# Power_Supply.net
KiCad netlist of a schematic drawn in EAGLE
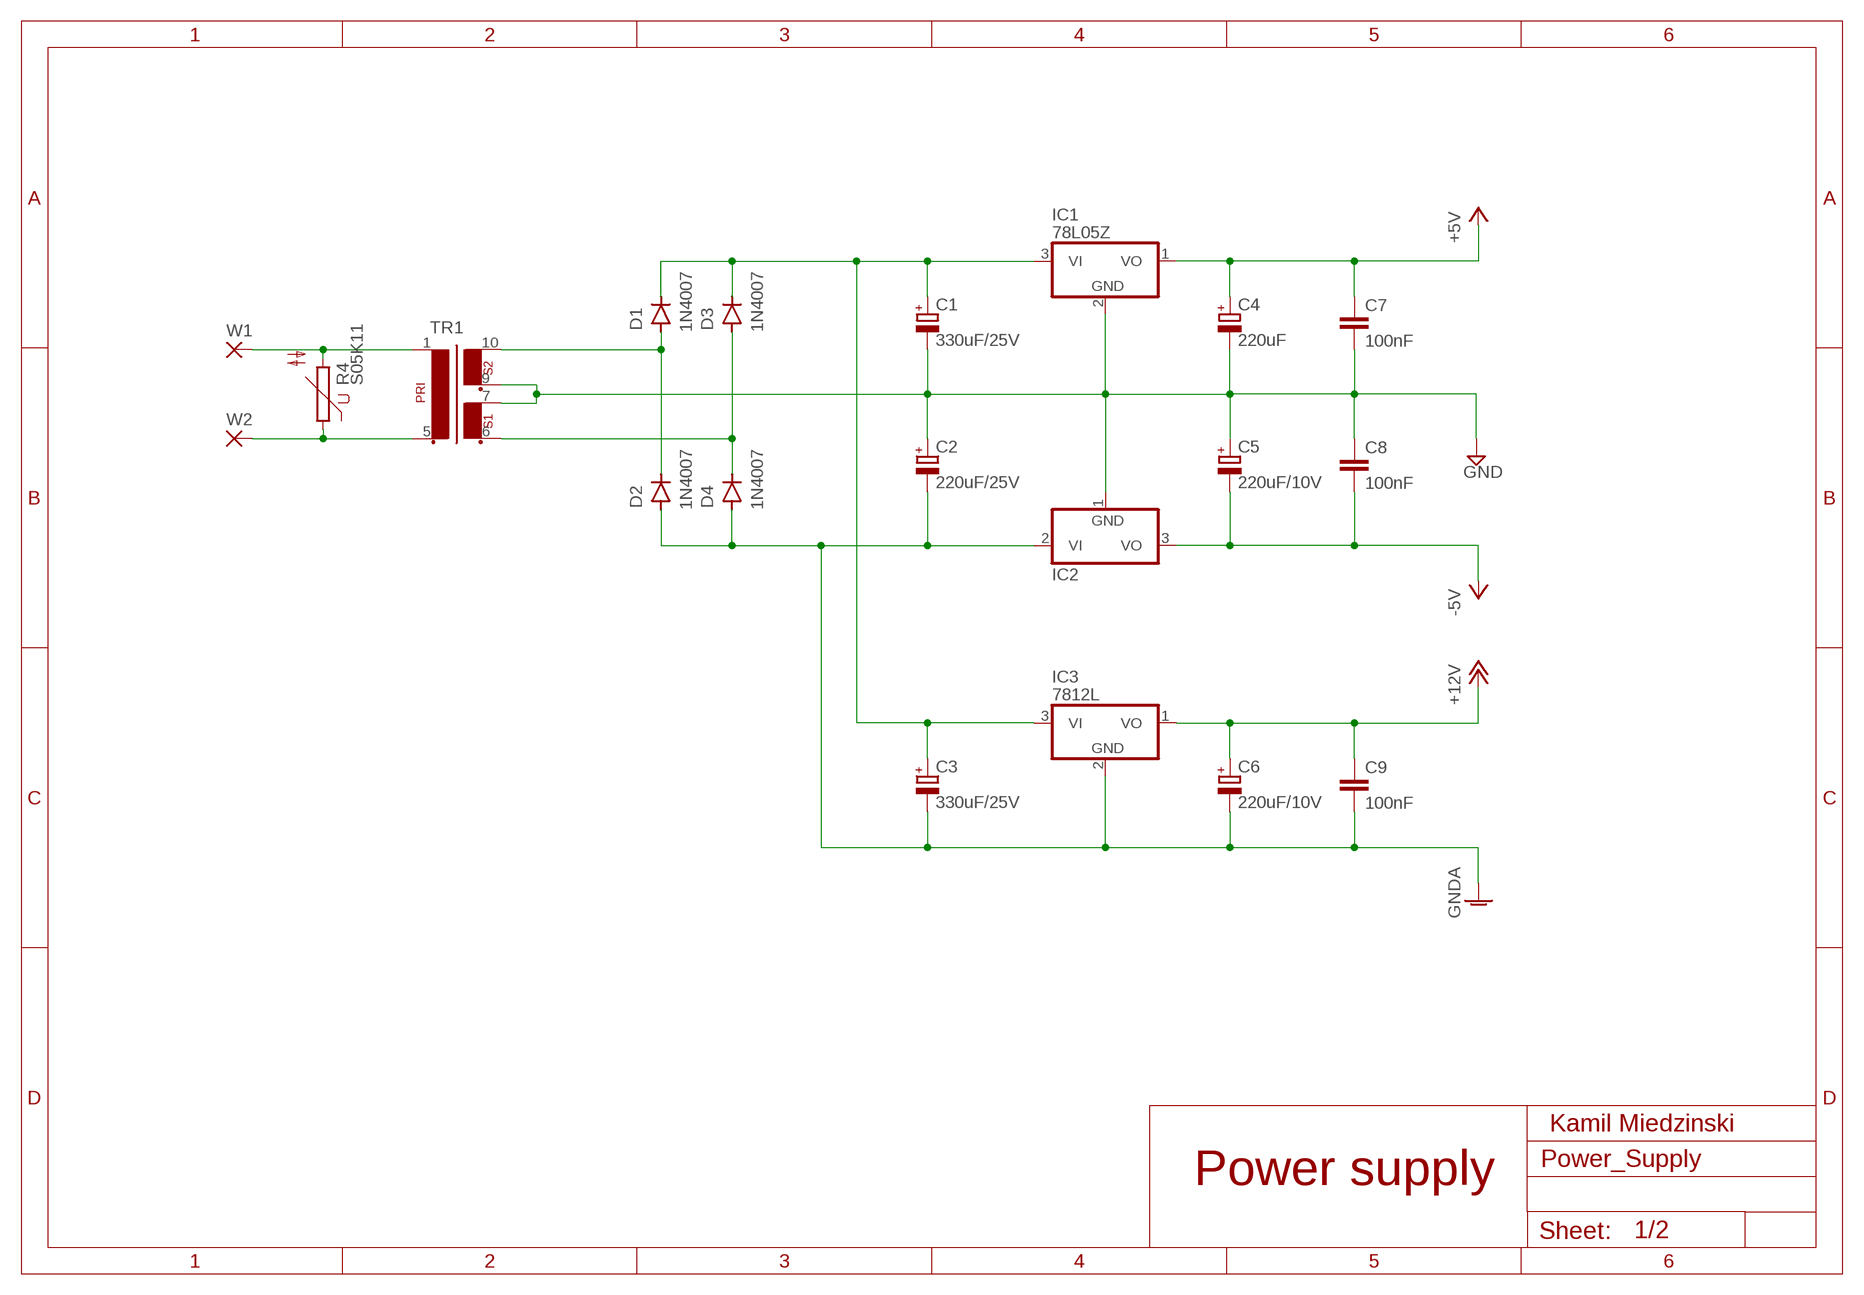
[diagram p0: schematic, sheet 1]
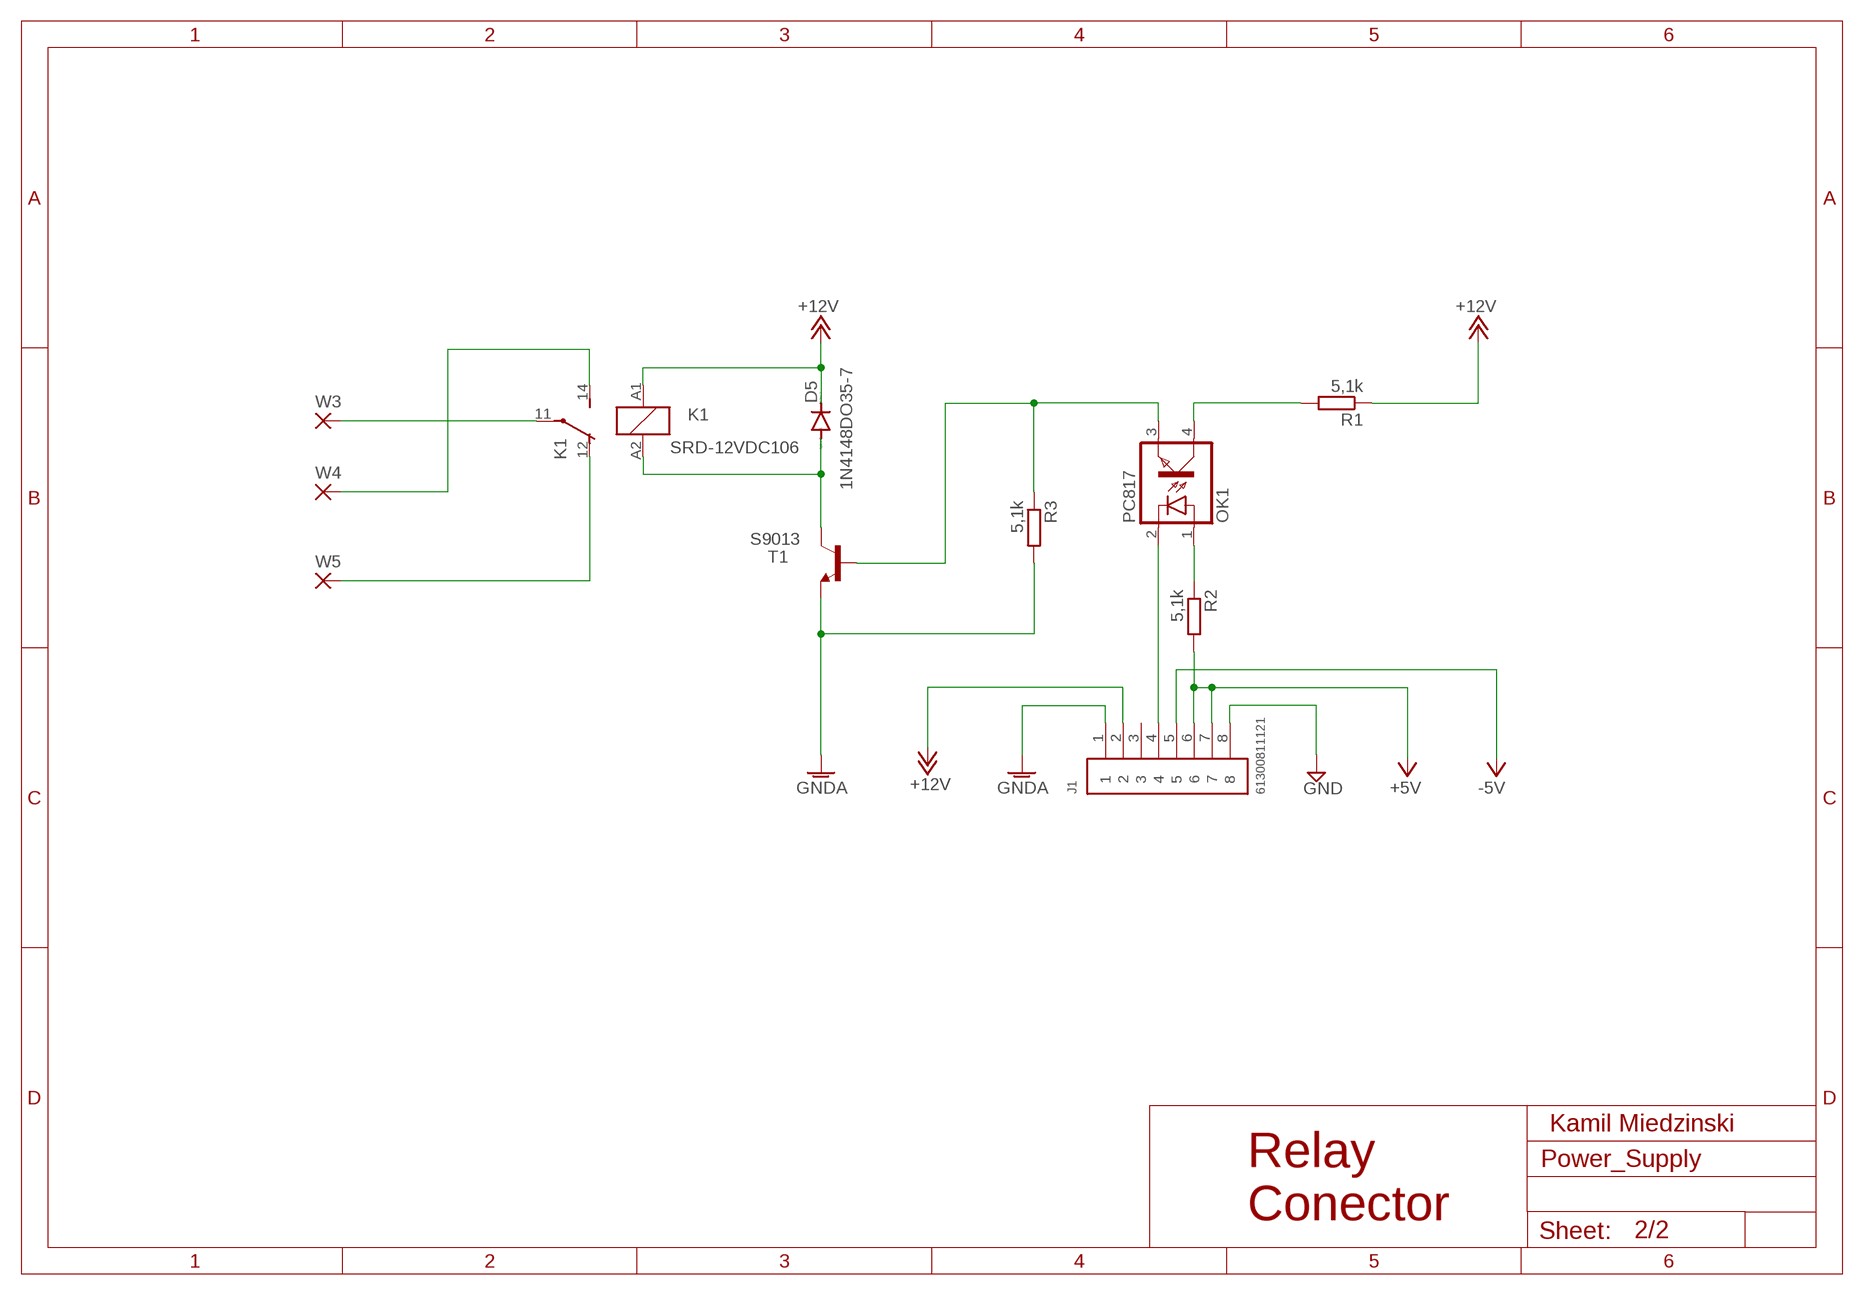
[diagram p1: schematic, sheet 2]

(export (version "E")
  (design (tool "Eeschema 10.0.6"))
  (components
    (comp (ref "D5")
      (value "1N4148DO35-7")
      (footprint "eagle-import:DO35-7")
      (libsource (lib "eagle-import") (part "1N4148DO35-7"))
    )
    (comp (ref "J1")
      (value "61300811121")
      (footprint "eagle-import:61300811121")
      (fields
        (field (name "DIGI_KEY_PART_NUMBER") "732-5321-ND")
        (field (name "MANUFACTURER") "Wurth Electronics Inc.")
        (field (name "CREATED_BY") "PCBLayout.com")
      )
      (libsource (lib "eagle-import") (part "61300811121"))
    )
    (comp (ref "K1")
      (value "SRD-12VDC106")
      (footprint "eagle-import:ZN5")
      (libsource (lib "eagle-import") (part "SRD-12VDC106"))
    )
    (comp (ref "OK1")
      (value "PC817")
      (footprint "eagle-import:DIL04")
      (fields (field (name "MPN") "PC817X4J000F"))
      (libsource (lib "eagle-import") (part "PC817"))
    )
    (comp (ref "R1")
      (value "5,1k")
      (footprint "eagle-import:0204_7")
      (libsource (lib "eagle-import") (part "R-EU_0204/7"))
    )
    (comp (ref "R2")
      (value "5,1k")
      (footprint "eagle-import:0204_7")
      (libsource (lib "eagle-import") (part "R-EU_0204/7"))
    )
    (comp (ref "R3")
      (value "5,1k")
      (footprint "eagle-import:0204_7")
      (libsource (lib "eagle-import") (part "R-EU_0204/7"))
    )
    (comp (ref "T1")
      (value "S9013")
      (footprint "eagle-import:TO92")
      (libsource (lib "eagle-import") (part "BC547"))
    )
    (comp (ref "W3")
      (value "PAD_4/7")
      (footprint "eagle-import:4_7")
      (libsource (lib "eagle-import") (part "PAD_4/7"))
    )
    (comp (ref "W4")
      (value "PAD_4/7")
      (footprint "eagle-import:4_7")
      (libsource (lib "eagle-import") (part "PAD_4/7"))
    )
    (comp (ref "W5")
      (value "PAD_4/7")
      (footprint "eagle-import:4_7")
      (libsource (lib "eagle-import") (part "PAD_4/7"))
    )
    (comp (ref "C1")
      (value "330uF/25V")
      (footprint "eagle-import:E3,5-8")
      (libsource (lib "eagle-import") (part "CPOL-EUE3.5-8"))
    )
    (comp (ref "C2")
      (value "220uF/25V")
      (footprint "eagle-import:E2,5-5")
      (libsource (lib "eagle-import") (part "CPOL-EUE2.5-5"))
    )
    (comp (ref "C3")
      (value "330uF/25V")
      (footprint "eagle-import:E3,5-8")
      (libsource (lib "eagle-import") (part "CPOL-EUE3.5-8"))
    )
    (comp (ref "C4")
      (value "220uF")
      (footprint "eagle-import:E2-4")
      (libsource (lib "eagle-import") (part "CPOL-EUE2-4"))
    )
    (comp (ref "C5")
      (value "220uF/10V")
      (footprint "eagle-import:E2-4")
      (libsource (lib "eagle-import") (part "CPOL-EUE2-4"))
    )
    (comp (ref "C6")
      (value "220uF/10V")
      (footprint "eagle-import:E2-4")
      (libsource (lib "eagle-import") (part "CPOL-EUE2-4"))
    )
    (comp (ref "C7")
      (value "100nF")
      (footprint "eagle-import:C025-024X044")
      (libsource (lib "eagle-import") (part "C-EU025-024X044"))
    )
    (comp (ref "C8")
      (value "100nF")
      (footprint "eagle-import:C025-024X044")
      (libsource (lib "eagle-import") (part "C-EU025-024X044"))
    )
    (comp (ref "C9")
      (value "100nF")
      (footprint "eagle-import:C025-024X044")
      (libsource (lib "eagle-import") (part "C-EU025-024X044"))
    )
    (comp (ref "D1")
      (value "1N4007")
      (footprint "eagle-import:DO-41")
      (fields
        (field (name "DIGIKEY_PART_NUMBER") "1N4007MSCT-ND")
        (field (name "MANUFACTURER") "Micro Commercial Co")
        (field (name "CREATED_BY") "PCBLayout.com")
      )
      (libsource (lib "eagle-import") (part "1N4007"))
    )
    (comp (ref "D2")
      (value "1N4007")
      (footprint "eagle-import:DO-41")
      (fields
        (field (name "DIGIKEY_PART_NUMBER") "1N4007MSCT-ND")
        (field (name "MANUFACTURER") "Micro Commercial Co")
        (field (name "CREATED_BY") "PCBLayout.com")
      )
      (libsource (lib "eagle-import") (part "1N4007"))
    )
    (comp (ref "D3")
      (value "1N4007")
      (footprint "eagle-import:DO-41")
      (fields
        (field (name "DIGIKEY_PART_NUMBER") "1N4007MSCT-ND")
        (field (name "MANUFACTURER") "Micro Commercial Co")
        (field (name "CREATED_BY") "PCBLayout.com")
      )
      (libsource (lib "eagle-import") (part "1N4007"))
    )
    (comp (ref "D4")
      (value "1N4007")
      (footprint "eagle-import:DO-41")
      (fields
        (field (name "DIGIKEY_PART_NUMBER") "1N4007MSCT-ND")
        (field (name "MANUFACTURER") "Micro Commercial Co")
        (field (name "CREATED_BY") "PCBLayout.com")
      )
      (libsource (lib "eagle-import") (part "1N4007"))
    )
    (comp (ref "IC1")
      (value "78L05Z")
      (footprint "eagle-import:TO92")
      (libsource (lib "eagle-import") (part "78ZL05"))
    )
    (comp (ref "IC2")
      (value "79L05Z")
      (footprint "eagle-import:TO92")
      (libsource (lib "eagle-import") (part "79ZL05"))
    )
    (comp (ref "IC3")
      (value "7812L")
      (footprint "eagle-import:TO92")
      (libsource (lib "eagle-import") (part "78L12"))
    )
    (comp (ref "R4")
      (value "S05K11")
      (footprint "eagle-import:S05K11")
      (libsource (lib "eagle-import") (part "S05K11"))
    )
    (comp (ref "TR1")
      (value "TEZ_2.0VA/230V/2X9V")
      (footprint "eagle-import:TEZ_2.0VA_230V_2X9V")
      (libsource (lib "eagle-import") (part "TEZ_2.0VA/230V/2X9V"))
    )
    (comp (ref "W1")
      (value "PAD_4/7")
      (footprint "eagle-import:4_7")
      (libsource (lib "eagle-import") (part "PAD_4/7"))
    )
    (comp (ref "W2")
      (value "PAD_4/7")
      (footprint "eagle-import:4_7")
      (libsource (lib "eagle-import") (part "PAD_4/7"))
    )
  )
  (nets
    (net (code "1") (name "+5V") (class "Default")
      (node (ref "C4") (pin "+") (pinfunction "+_+") (pintype "passive"))
      (node (ref "C7") (pin "1") (pinfunction "1_1") (pintype "passive"))
      (node (ref "IC1") (pin "1") (pinfunction "VO_1") (pintype "passive"))
      (node (ref "J1") (pin "6") (pinfunction "6_6") (pintype "passive"))
      (node (ref "J1") (pin "7") (pinfunction "7_7") (pintype "passive"))
      (node (ref "R2") (pin "2") (pinfunction "2_2") (pintype "passive"))
    )
    (net (code "2") (name "+12V") (class "Default")
      (node (ref "C6") (pin "+") (pinfunction "+_+") (pintype "passive"))
      (node (ref "C9") (pin "1") (pinfunction "1_1") (pintype "passive"))
      (node (ref "D5") (pin "C") (pinfunction "C_C") (pintype "passive"))
      (node (ref "IC3") (pin "1") (pinfunction "VO_1") (pintype "passive"))
      (node (ref "J1") (pin "2") (pinfunction "2_2") (pintype "passive"))
      (node (ref "K1") (pin "A1") (pinfunction "1_A1") (pintype "passive"))
      (node (ref "R1") (pin "1") (pinfunction "1_1") (pintype "passive"))
    )
    (net (code "3") (name "-5V") (class "Default")
      (node (ref "C5") (pin "-") (pinfunction "-_-") (pintype "passive"))
      (node (ref "C8") (pin "2") (pinfunction "2_2") (pintype "passive"))
      (node (ref "IC2") (pin "3") (pinfunction "VO_3") (pintype "passive"))
      (node (ref "J1") (pin "5") (pinfunction "5_5") (pintype "passive"))
    )
    (net (code "4") (name "GND") (class "Default")
      (node (ref "C1") (pin "-") (pinfunction "-_-") (pintype "passive"))
      (node (ref "C2") (pin "+") (pinfunction "+_+") (pintype "passive"))
      (node (ref "C4") (pin "-") (pinfunction "-_-") (pintype "passive"))
      (node (ref "C5") (pin "+") (pinfunction "+_+") (pintype "passive"))
      (node (ref "C7") (pin "2") (pinfunction "2_2") (pintype "passive"))
      (node (ref "C8") (pin "1") (pinfunction "1_1") (pintype "passive"))
      (node (ref "IC1") (pin "2") (pinfunction "GND_2") (pintype "passive"))
      (node (ref "IC2") (pin "1") (pinfunction "GND_1") (pintype "passive"))
      (node (ref "J1") (pin "8") (pinfunction "8_8") (pintype "passive"))
      (node (ref "TR1") (pin "7") (pinfunction "4_7") (pintype "passive"))
      (node (ref "TR1") (pin "9") (pinfunction "5_9") (pintype "passive"))
    )
    (net (code "5") (name "GNDA") (class "Default")
      (node (ref "C2") (pin "-") (pinfunction "-_-") (pintype "passive"))
      (node (ref "C3") (pin "-") (pinfunction "-_-") (pintype "passive"))
      (node (ref "C6") (pin "-") (pinfunction "-_-") (pintype "passive"))
      (node (ref "C9") (pin "2") (pinfunction "2_2") (pintype "passive"))
      (node (ref "D2") (pin "A") (pinfunction "A_A") (pintype "passive"))
      (node (ref "D4") (pin "A") (pinfunction "A_A") (pintype "passive"))
      (node (ref "IC2") (pin "2") (pinfunction "VI_2") (pintype "input"))
      (node (ref "IC3") (pin "2") (pinfunction "GND_2") (pintype "passive"))
      (node (ref "J1") (pin "1") (pinfunction "1_1") (pintype "passive"))
      (node (ref "R3") (pin "2") (pinfunction "2_2") (pintype "passive"))
      (node (ref "T1") (pin "1") (pinfunction "E_1") (pintype "passive"))
    )
    (net (code "6") (name "Net-(IC1-VI)") (class "Default")
      (node (ref "C1") (pin "+") (pinfunction "+_+") (pintype "passive"))
      (node (ref "C3") (pin "+") (pinfunction "+_+") (pintype "passive"))
      (node (ref "D1") (pin "C") (pinfunction "C_C") (pintype "passive"))
      (node (ref "D3") (pin "C") (pinfunction "C_C") (pintype "passive"))
      (node (ref "IC1") (pin "3") (pinfunction "VI_3") (pintype "input"))
      (node (ref "IC3") (pin "3") (pinfunction "VI_3") (pintype "input"))
    )
    (net (code "7") (name "Net-(K1A-2)") (class "Default")
      (node (ref "D5") (pin "A") (pinfunction "A_A") (pintype "passive"))
      (node (ref "K1") (pin "A2") (pinfunction "2_A2") (pintype "passive"))
      (node (ref "T1") (pin "3") (pinfunction "C_3") (pintype "passive"))
    )
    (net (code "8") (name "Net-(K1B-O)") (class "Default")
      (node (ref "K1") (pin "12") (pinfunction "O_12") (pintype "passive"))
      (node (ref "W5") (pin "1") (pinfunction "P_1") (pintype "passive"))
    )
    (net (code "9") (name "Net-(K1B-P)") (class "Default")
      (node (ref "K1") (pin "11") (pinfunction "P_11") (pintype "passive"))
      (node (ref "W3") (pin "1") (pinfunction "P_1") (pintype "passive"))
    )
    (net (code "10") (name "Net-(K1B-S)") (class "Default")
      (node (ref "K1") (pin "14") (pinfunction "S_14") (pintype "passive"))
      (node (ref "W4") (pin "1") (pinfunction "P_1") (pintype "passive"))
    )
    (net (code "11") (name "Net-(OK1-A)") (class "Default")
      (node (ref "OK1") (pin "1") (pinfunction "A_1") (pintype "passive"))
      (node (ref "R2") (pin "1") (pinfunction "1_1") (pintype "passive"))
    )
    (net (code "12") (name "Net-(OK1-C)") (class "Default")
      (node (ref "J1") (pin "4") (pinfunction "4_4") (pintype "passive"))
      (node (ref "OK1") (pin "2") (pinfunction "C_2") (pintype "passive"))
    )
    (net (code "13") (name "Net-(OK1-COL)") (class "Default")
      (node (ref "OK1") (pin "4") (pinfunction "COL_4") (pintype "passive"))
      (node (ref "R1") (pin "2") (pinfunction "2_2") (pintype "passive"))
    )
    (net (code "14") (name "Net-(OK1-EMIT)") (class "Default")
      (node (ref "OK1") (pin "3") (pinfunction "EMIT_3") (pintype "passive"))
      (node (ref "R3") (pin "1") (pinfunction "1_1") (pintype "passive"))
      (node (ref "T1") (pin "2") (pinfunction "B_2") (pintype "passive"))
    )
    (net (code "15") (name "Net-(TR1-2)") (class "Default")
      (node (ref "R4") (pin "1") (pinfunction "1_1") (pintype "passive"))
      (node (ref "TR1") (pin "5") (pinfunction "2_5") (pintype "passive"))
      (node (ref "W2") (pin "1") (pinfunction "P_1") (pintype "passive"))
    )
    (net (code "16") (name "Net-(TR1-3)") (class "Default")
      (node (ref "D3") (pin "A") (pinfunction "A_A") (pintype "passive"))
      (node (ref "D4") (pin "C") (pinfunction "C_C") (pintype "passive"))
      (node (ref "TR1") (pin "6") (pinfunction "3_6") (pintype "passive"))
    )
    (net (code "17") (name "Net-(TR1-6)") (class "Default")
      (node (ref "D1") (pin "A") (pinfunction "A_A") (pintype "passive"))
      (node (ref "D2") (pin "C") (pinfunction "C_C") (pintype "passive"))
      (node (ref "TR1") (pin "10") (pinfunction "6_10") (pintype "passive"))
    )
    (net (code "18") (name "Net-(W1-P)") (class "Default")
      (node (ref "R4") (pin "2") (pinfunction "2_2") (pintype "passive"))
      (node (ref "TR1") (pin "1") (pinfunction "1_1") (pintype "passive"))
      (node (ref "W1") (pin "1") (pinfunction "P_1") (pintype "passive"))
    )
    (net (code "19") (name "unconnected-(J1-Pad3)") (class "Default")
      (node (ref "J1") (pin "3") (pinfunction "3_3") (pintype "passive"))
    )
  )
)
